# Drop_sensor.net
KiCad netlist of a schematic drawn in EasyEDA
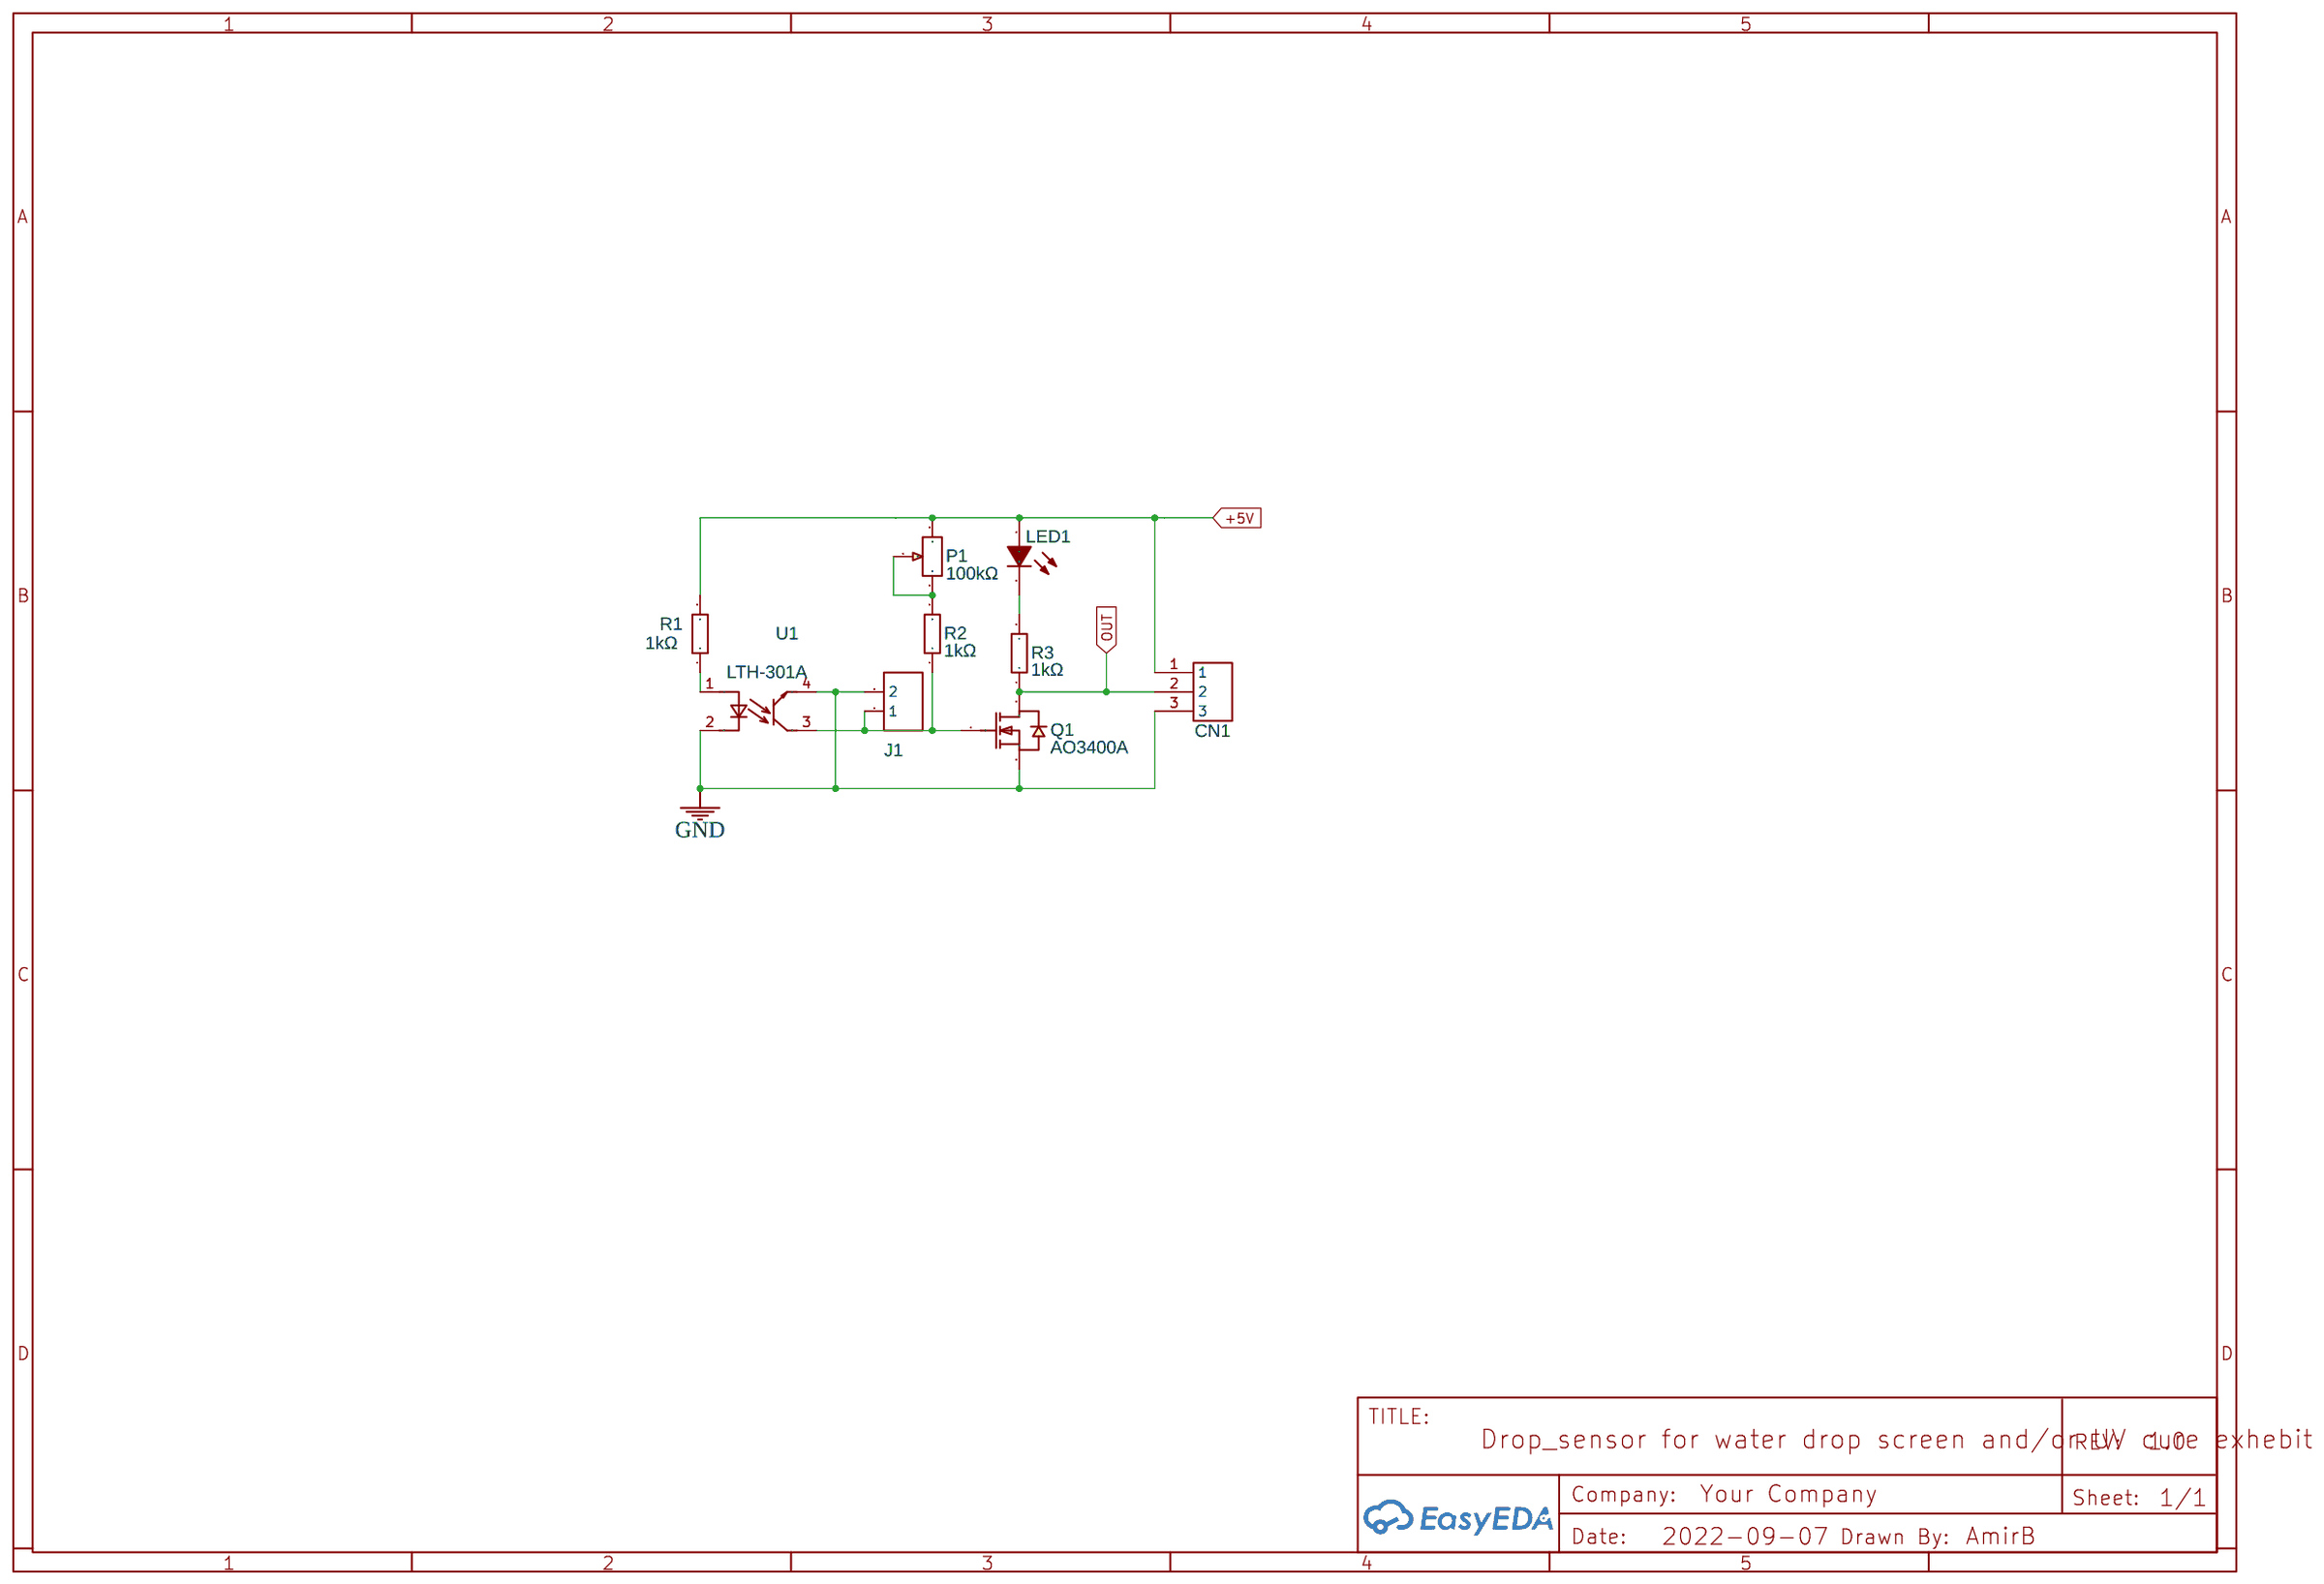
[diagram p0: schematic sheet]

(export (version "E")
  (design (tool "Eeschema 10.0.6"))
  (components
    (comp (ref "CN1")
      (value "XHB-3A")
      (fields (field (name "BOM_Supplier Part") "C68817"))
      (libsource (lib "") (part "XHB-3A"))
    )
    (comp (ref "J1")
      (value "HDR-M-2.54_1x2")
      (fields (field (name "BOM_Supplier Part") "C124375"))
      (libsource (lib "") (part "HDR-M-2.54_1x2"))
    )
    (comp (ref "LED1")
      (value "19-217/BHC-ZL1M2RY/3T")
      (fields (field (name "BOM_Supplier Part") "C72041"))
      (libsource (lib "") (part "19-217/BHC-ZL1M2RY/3T"))
    )
    (comp (ref "P1")
      (value "100kΩ")
      (fields
        (field (name "BOM_Manufacturer Part") "3296W-1-104")
        (field (name "BOM_Supplier Part") "C118963")
      )
      (libsource (lib "") (part "3296W-1-104"))
    )
    (comp (ref "Q1")
      (value "AO3400A")
      (fields (field (name "BOM_Supplier Part") "C20917"))
      (libsource (lib "") (part "AO3400A"))
    )
    (comp (ref "R1")
      (value "1kΩ")
      (fields
        (field (name "BOM_Manufacturer Part") "0603WAF1001T5E")
        (field (name "BOM_Supplier Part") "C21190")
      )
      (libsource (lib "") (part "0603WAF1001T5E"))
    )
    (comp (ref "R2")
      (value "1kΩ")
      (fields
        (field (name "BOM_Manufacturer Part") "0603WAF1001T5E")
        (field (name "BOM_Supplier Part") "C21190")
      )
      (libsource (lib "") (part "0603WAF1001T5E"))
    )
    (comp (ref "R3")
      (value "1kΩ")
      (fields
        (field (name "BOM_Manufacturer Part") "0603WAF1001T5E")
        (field (name "BOM_Supplier Part") "C21190")
      )
      (libsource (lib "") (part "0603WAF1001T5E"))
    )
    (comp (ref "U1")
      (value "LTH-301A")
      (fields (field (name "BOM_Supplier Part") "C115445"))
      (libsource (lib "") (part "LTH-301A"))
    )
  )
  (nets
    (net (code "1") (name "+5V") (class "Default")
      (node (ref "CN1") (pin "1") (pinfunction "1_1") (pintype "unspecified"))
      (node (ref "LED1") (pin "1") (pinfunction "A_1") (pintype "input"))
      (node (ref "P1") (pin "3") (pinfunction "3_3") (pintype "input"))
      (node (ref "R1") (pin "2") (pinfunction "2_2") (pintype "input"))
    )
    (net (code "2") (name "GND") (class "Default")
      (node (ref "CN1") (pin "3") (pinfunction "3_3") (pintype "unspecified"))
      (node (ref "J1") (pin "2") (pinfunction "2_2") (pintype "unspecified"))
      (node (ref "Q1") (pin "2") (pinfunction "S_2") (pintype "unspecified"))
      (node (ref "U1") (pin "2") (pinfunction "2_2") (pintype "unspecified"))
      (node (ref "U1") (pin "4") (pinfunction "4_4") (pintype "unspecified"))
    )
    (net (code "3") (name "Net-(LED1-C)") (class "Default")
      (node (ref "LED1") (pin "2") (pinfunction "C_2") (pintype "input"))
      (node (ref "R3") (pin "2") (pinfunction "2_2") (pintype "input"))
    )
    (net (code "4") (name "Net-(P1-Pad1)") (class "Default")
      (node (ref "P1") (pin "1") (pinfunction "1_1") (pintype "input"))
      (node (ref "P1") (pin "2") (pinfunction "2_2") (pintype "input"))
      (node (ref "R2") (pin "2") (pinfunction "2_2") (pintype "input"))
    )
    (net (code "5") (name "Net-(Q1-G)") (class "Default")
      (node (ref "J1") (pin "1") (pinfunction "1_1") (pintype "unspecified"))
      (node (ref "Q1") (pin "1") (pinfunction "G_1") (pintype "unspecified"))
      (node (ref "R2") (pin "1") (pinfunction "1_1") (pintype "input"))
      (node (ref "U1") (pin "3") (pinfunction "3_3") (pintype "unspecified"))
    )
    (net (code "6") (name "Net-(R1-Pad1)") (class "Default")
      (node (ref "R1") (pin "1") (pinfunction "1_1") (pintype "input"))
      (node (ref "U1") (pin "1") (pinfunction "1_1") (pintype "unspecified"))
    )
    (net (code "7") (name "OUT") (class "Default")
      (node (ref "CN1") (pin "2") (pinfunction "2_2") (pintype "unspecified"))
      (node (ref "Q1") (pin "3") (pinfunction "D_3") (pintype "unspecified"))
      (node (ref "R3") (pin "1") (pinfunction "1_1") (pintype "input"))
    )
  )
)
